# strain-gauge-amplifier-v1.net
KiCad netlist of a schematic drawn in EAGLE
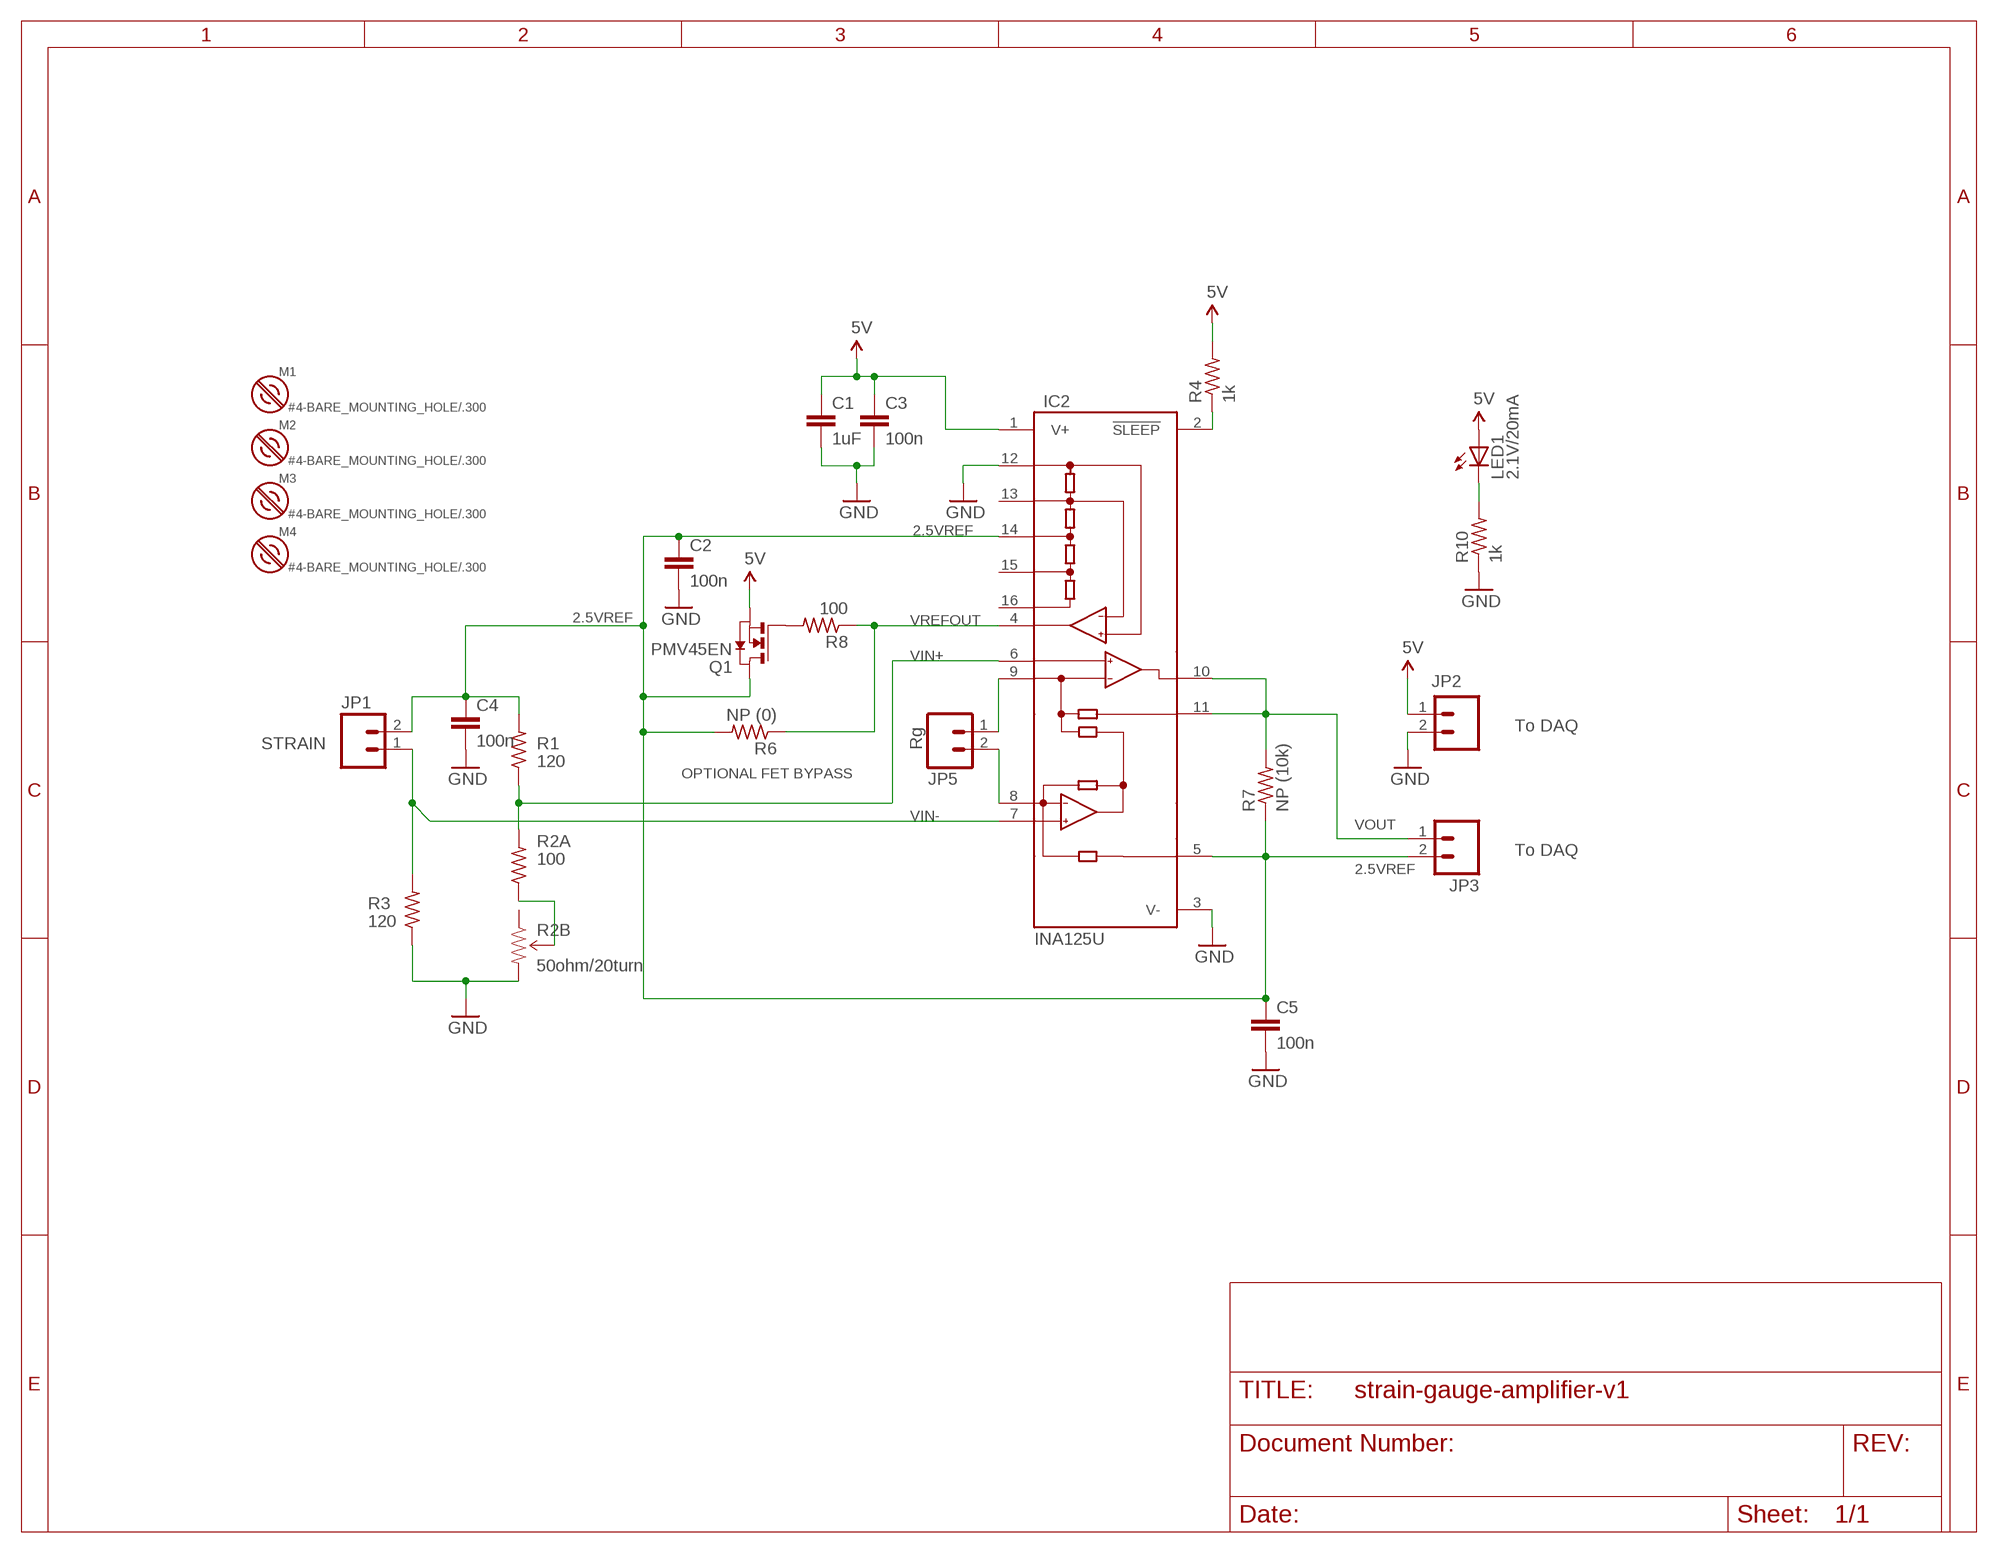
[diagram p0: schematic, sheet 1]

(export (version "E")
  (design (tool "Eeschema 10.0.6"))
  (components
    (comp (ref "C1")
      (value "1uF")
      (footprint "eagle-import:0805-C-NOSILK")
      (libsource (lib "eagle-import") (part "C-EU0805-C-NOSILK"))
    )
    (comp (ref "C2")
      (value "100n")
      (footprint "eagle-import:0805-C-NOSILK")
      (libsource (lib "eagle-import") (part "C-EU0805-C-NOSILK"))
    )
    (comp (ref "C3")
      (value "100n")
      (footprint "eagle-import:0805-C-NOSILK")
      (libsource (lib "eagle-import") (part "C-EU0805-C-NOSILK"))
    )
    (comp (ref "C4")
      (value "100n")
      (footprint "eagle-import:0805-C-NOSILK")
      (libsource (lib "eagle-import") (part "C-EU0805-C-NOSILK"))
    )
    (comp (ref "C5")
      (value "100n")
      (footprint "eagle-import:0805-C-NOSILK")
      (libsource (lib "eagle-import") (part "C-EU0805-C-NOSILK"))
    )
    (comp (ref "IC2")
      (value "INA125U")
      (footprint "eagle-import:SO16-1")
      (fields (field (name "MF") "TEXAS INSTRUMENT CONNECTORS"))
      (libsource (lib "eagle-import") (part "INA125U"))
    )
    (comp (ref "JP1")
      (value "STRAIN")
      (footprint "eagle-import:SCREWTERMINAL-5MM-2")
      (libsource (lib "eagle-import") (part "M025MM"))
    )
    (comp (ref "JP2")
      (value "M025MM")
      (footprint "eagle-import:SCREWTERMINAL-5MM-2")
      (libsource (lib "eagle-import") (part "M025MM"))
    )
    (comp (ref "JP3")
      (value "M025MM")
      (footprint "eagle-import:SCREWTERMINAL-5MM-2")
      (libsource (lib "eagle-import") (part "M025MM"))
    )
    (comp (ref "JP5")
      (value "Rg")
      (footprint "eagle-import:SCREWTERMINAL-5MM-2")
      (libsource (lib "eagle-import") (part "M025MM"))
    )
    (comp (ref "LED1")
      (value "2.1V/20mA")
      (footprint "eagle-import:LED-0603")
      (libsource (lib "eagle-import") (part "LED0603"))
    )
    (comp (ref "M1")
      (value "#4-BARE_MOUNTING_HOLE/.300")
      (footprint "eagle-import:#4_.300-BARE+STD_NUT_OR_STAR_WASHER")
      (libsource (lib "eagle-import") (part "#4-BARE_MOUNTING_HOLE/.300"))
    )
    (comp (ref "M2")
      (value "#4-BARE_MOUNTING_HOLE/.300")
      (footprint "eagle-import:#4_.300-BARE+STD_NUT_OR_STAR_WASHER")
      (libsource (lib "eagle-import") (part "#4-BARE_MOUNTING_HOLE/.300"))
    )
    (comp (ref "M3")
      (value "#4-BARE_MOUNTING_HOLE/.300")
      (footprint "eagle-import:#4_.300-BARE+STD_NUT_OR_STAR_WASHER")
      (libsource (lib "eagle-import") (part "#4-BARE_MOUNTING_HOLE/.300"))
    )
    (comp (ref "M4")
      (value "#4-BARE_MOUNTING_HOLE/.300")
      (footprint "eagle-import:#4_.300-BARE+STD_NUT_OR_STAR_WASHER")
      (libsource (lib "eagle-import") (part "#4-BARE_MOUNTING_HOLE/.300"))
    )
    (comp (ref "Q1")
      (value "PMV45EN")
      (footprint "eagle-import:SOT23")
      (libsource (lib "eagle-import") (part "PMV45EN"))
    )
    (comp (ref "R1")
      (value "120")
      (footprint "eagle-import:0805-C-NOSILK")
      (libsource (lib "eagle-import") (part "R-US_0805-C-NOSILK"))
    )
    (comp (ref "R2A")
      (value "100")
      (footprint "eagle-import:0805-C-NOSILK")
      (libsource (lib "eagle-import") (part "R-US_0805-C-NOSILK"))
    )
    (comp (ref "R2B")
      (value "50ohm/20turn")
      (footprint "eagle-import:TRIMPOT-5MM")
      (libsource (lib "eagle-import") (part "TRIMPOTTRIMPOT-5MM"))
    )
    (comp (ref "R3")
      (value "120")
      (footprint "eagle-import:0805-C-NOSILK")
      (libsource (lib "eagle-import") (part "R-US_0805-C-NOSILK"))
    )
    (comp (ref "R4")
      (value "1k")
      (footprint "eagle-import:0805-C-NOSILK")
      (libsource (lib "eagle-import") (part "R-US_0805-C-NOSILK"))
    )
    (comp (ref "R6")
      (value "NP (0)")
      (footprint "eagle-import:0805-C-NOSILK")
      (libsource (lib "eagle-import") (part "R-US_0805-C-NOSILK"))
    )
    (comp (ref "R7")
      (value "NP (10k)")
      (footprint "eagle-import:0805-C-NOSILK")
      (libsource (lib "eagle-import") (part "R-US_0805-C-NOSILK"))
    )
    (comp (ref "R8")
      (value "100")
      (footprint "eagle-import:0805-C-NOSILK")
      (libsource (lib "eagle-import") (part "R-US_0805-C-NOSILK"))
    )
    (comp (ref "R10")
      (value "1k")
      (footprint "eagle-import:0805-C-NOSILK")
      (libsource (lib "eagle-import") (part "R-US_0805-C-NOSILK"))
    )
  )
  (nets
    (net (code "1") (name "/2.5VREF") (class "Default")
      (node (ref "C2") (pin "1") (pinfunction "1_1") (pintype "passive"))
      (node (ref "C4") (pin "1") (pinfunction "1_1") (pintype "passive"))
      (node (ref "C5") (pin "1") (pinfunction "1_1") (pintype "passive"))
      (node (ref "IC2") (pin "14") (pinfunction "REF2.5_14") (pintype "output"))
      (node (ref "IC2") (pin "5") (pinfunction "REF_5") (pintype "passive"))
      (node (ref "JP1") (pin "2") (pinfunction "2_2") (pintype "passive"))
      (node (ref "JP3") (pin "2") (pinfunction "2_2") (pintype "passive"))
      (node (ref "Q1") (pin "3") (pinfunction "D_3") (pintype "passive"))
      (node (ref "R1") (pin "2") (pinfunction "2_2") (pintype "passive"))
      (node (ref "R6") (pin "2") (pinfunction "2_2") (pintype "passive"))
      (node (ref "R7") (pin "1") (pinfunction "1_1") (pintype "passive"))
    )
    (net (code "2") (name "/VIN+") (class "Default")
      (node (ref "IC2") (pin "6") (pinfunction "+IN_6") (pintype "input"))
      (node (ref "R1") (pin "1") (pinfunction "1_1") (pintype "passive"))
      (node (ref "R2A") (pin "2") (pinfunction "2_2") (pintype "passive"))
    )
    (net (code "3") (name "/VIN-") (class "Default")
      (node (ref "IC2") (pin "7") (pinfunction "-VIN_7") (pintype "input"))
      (node (ref "JP1") (pin "1") (pinfunction "1_1") (pintype "passive"))
      (node (ref "R3") (pin "2") (pinfunction "2_2") (pintype "passive"))
    )
    (net (code "4") (name "/VOUT") (class "Default")
      (node (ref "IC2") (pin "10") (pinfunction "OUT_10") (pintype "output"))
      (node (ref "IC2") (pin "11") (pinfunction "SENSE_11") (pintype "passive"))
      (node (ref "JP3") (pin "1") (pinfunction "1_1") (pintype "passive"))
      (node (ref "R7") (pin "2") (pinfunction "2_2") (pintype "passive"))
    )
    (net (code "5") (name "/VREFOUT") (class "Default")
      (node (ref "IC2") (pin "4") (pinfunction "REFOUT_4") (pintype "output"))
      (node (ref "R6") (pin "1") (pinfunction "1_1") (pintype "passive"))
      (node (ref "R8") (pin "1") (pinfunction "1_1") (pintype "passive"))
    )
    (net (code "6") (name "5V") (class "Default")
      (node (ref "C1") (pin "1") (pinfunction "1_1") (pintype "passive"))
      (node (ref "C3") (pin "1") (pinfunction "1_1") (pintype "passive"))
      (node (ref "IC2") (pin "1") (pinfunction "V+_1") (pintype "power_in"))
      (node (ref "JP2") (pin "1") (pinfunction "1_1") (pintype "passive"))
      (node (ref "LED1") (pin "A") (pinfunction "A_A") (pintype "passive"))
      (node (ref "Q1") (pin "2") (pinfunction "S_2") (pintype "passive"))
      (node (ref "R4") (pin "2") (pinfunction "2_2") (pintype "passive"))
    )
    (net (code "7") (name "GND") (class "Default")
      (node (ref "C1") (pin "2") (pinfunction "2_2") (pintype "passive"))
      (node (ref "C2") (pin "2") (pinfunction "2_2") (pintype "passive"))
      (node (ref "C3") (pin "2") (pinfunction "2_2") (pintype "passive"))
      (node (ref "C4") (pin "2") (pinfunction "2_2") (pintype "passive"))
      (node (ref "C5") (pin "2") (pinfunction "2_2") (pintype "passive"))
      (node (ref "IC2") (pin "12") (pinfunction "REFCOM_12") (pintype "passive"))
      (node (ref "IC2") (pin "3") (pinfunction "V-_3") (pintype "power_in"))
      (node (ref "JP2") (pin "2") (pinfunction "2_2") (pintype "passive"))
      (node (ref "R10") (pin "1") (pinfunction "1_1") (pintype "passive"))
      (node (ref "R2B") (pin "C") (pinfunction "CW_C") (pintype "passive"))
      (node (ref "R3") (pin "1") (pinfunction "1_1") (pintype "passive"))
    )
    (net (code "8") (name "Net-(IC2-RG-Pad8)") (class "Default")
      (node (ref "IC2") (pin "8") (pinfunction "RG_8") (pintype "passive"))
      (node (ref "JP5") (pin "2") (pinfunction "2_2") (pintype "passive"))
    )
    (net (code "9") (name "Net-(IC2-RG-Pad9)") (class "Default")
      (node (ref "IC2") (pin "9") (pinfunction "RG_9") (pintype "passive"))
      (node (ref "JP5") (pin "1") (pinfunction "1_1") (pintype "passive"))
    )
    (net (code "10") (name "Net-(IC2-~{SLEEP})") (class "Default")
      (node (ref "IC2") (pin "2") (pinfunction "~{SLEEP}_2") (pintype "input"))
      (node (ref "R4") (pin "1") (pinfunction "1_1") (pintype "passive"))
    )
    (net (code "11") (name "Net-(LED1-PadC)") (class "Default")
      (node (ref "LED1") (pin "C") (pinfunction "C_C") (pintype "passive"))
      (node (ref "R10") (pin "2") (pinfunction "2_2") (pintype "passive"))
    )
    (net (code "12") (name "Net-(Q1-G)") (class "Default")
      (node (ref "Q1") (pin "1") (pinfunction "G_1") (pintype "passive"))
      (node (ref "R8") (pin "2") (pinfunction "2_2") (pintype "passive"))
    )
    (net (code "13") (name "Net-(R2B-WIPER)") (class "Default")
      (node (ref "R2A") (pin "1") (pinfunction "1_1") (pintype "passive"))
      (node (ref "R2B") (pin "B") (pinfunction "WIPER_B") (pintype "passive"))
    )
    (net (code "14") (name "unconnected-(IC2-REF5-Pad15)") (class "Default")
      (node (ref "IC2") (pin "15") (pinfunction "REF5_15") (pintype "output"))
    )
    (net (code "15") (name "unconnected-(IC2-REF10-Pad16)") (class "Default")
      (node (ref "IC2") (pin "16") (pinfunction "REF10_16") (pintype "output"))
    )
    (net (code "16") (name "unconnected-(IC2-REFBG-Pad13)") (class "Default")
      (node (ref "IC2") (pin "13") (pinfunction "REFBG_13") (pintype "output"))
    )
    (net (code "17") (name "unconnected-(R2B-CCW-PadA)") (class "Default")
      (node (ref "R2B") (pin "A") (pinfunction "CCW_A") (pintype "passive"))
    )
  )
)
